# LSM303_breakout_board-v12.net
KiCad netlist of a schematic drawn in EAGLE
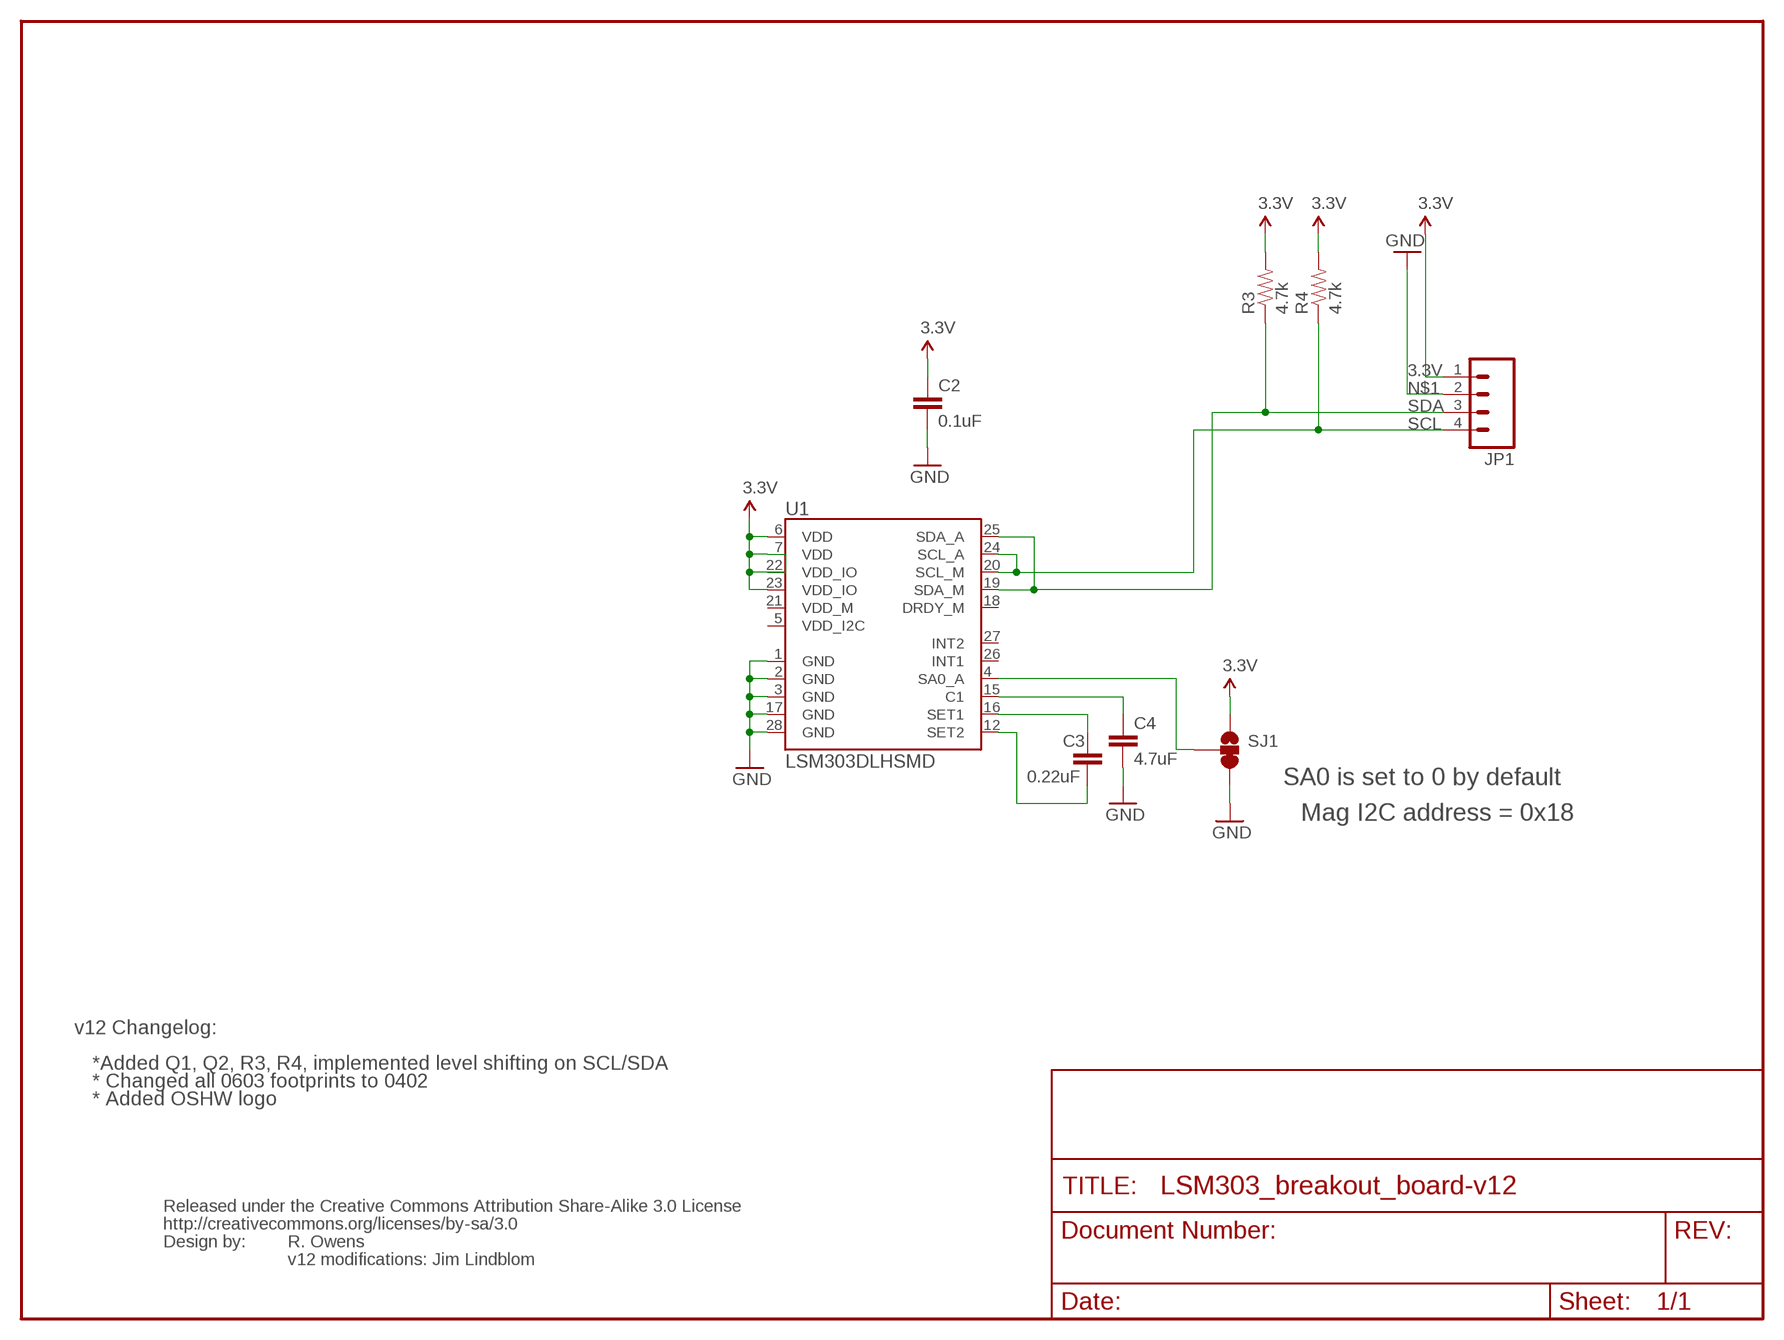
[diagram p0: schematic, sheet 1]

(export (version "E")
  (design (tool "Eeschema 10.0.6"))
  (components
    (comp (ref "C2")
      (value "0.1uF")
      (footprint "eagle-import:0603-CAP")
      (libsource (lib "eagle-import") (part "CAP0603-CAP"))
    )
    (comp (ref "C3")
      (value "0.22uF")
      (footprint "eagle-import:0603-CAP")
      (libsource (lib "eagle-import") (part "CAP0603-CAP"))
    )
    (comp (ref "C4")
      (value "4.7uF")
      (footprint "eagle-import:1206")
      (libsource (lib "eagle-import") (part "CAP1206"))
    )
    (comp (ref "JP1")
      (value "M04PTH")
      (footprint "eagle-import:1X04")
      (libsource (lib "eagle-import") (part "M04PTH"))
    )
    (comp (ref "R3")
      (value "4.7k")
      (footprint "eagle-import:0603-RES")
      (libsource (lib "eagle-import") (part "RESISTOR0603-RES"))
    )
    (comp (ref "R4")
      (value "4.7k")
      (footprint "eagle-import:0603-RES")
      (libsource (lib "eagle-import") (part "RESISTOR0603-RES"))
    )
    (comp (ref "SJ1")
      (value "SOLDERJUMPER_2WAYPASTE2&3")
      (footprint "eagle-import:SJ_3_PASTE2&3")
      (libsource (lib "eagle-import") (part "SOLDERJUMPER_2WAYPASTE2&3"))
    )
    (comp (ref "U$5")
      (value "CREATIVE_COMMONS")
      (footprint "eagle-import:CREATIVE_COMMONS")
      (libsource (lib "eagle-import") (part "CREATIVE_COMMONS"))
    )
    (comp (ref "U1")
      (value "LSM303DLHSMD")
      (footprint "eagle-import:LGA28-5X5")
      (libsource (lib "eagle-import") (part "LSM303DLHSMD"))
    )
  )
  (nets
    (net (code "1") (name "/SCL") (class "Default")
      (node (ref "JP1") (pin "4") (pinfunction "4_4") (pintype "passive"))
      (node (ref "R4") (pin "1") (pinfunction "1_1") (pintype "passive"))
      (node (ref "U1") (pin "20") (pinfunction "SCL_M_20") (pintype "bidirectional"))
      (node (ref "U1") (pin "24") (pinfunction "SCL_A_24") (pintype "bidirectional"))
    )
    (net (code "2") (name "/SDA") (class "Default")
      (node (ref "JP1") (pin "3") (pinfunction "3_3") (pintype "passive"))
      (node (ref "R3") (pin "1") (pinfunction "1_1") (pintype "passive"))
      (node (ref "U1") (pin "19") (pinfunction "SDA_M_19") (pintype "bidirectional"))
      (node (ref "U1") (pin "25") (pinfunction "SDA_A_25") (pintype "bidirectional"))
    )
    (net (code "3") (name "3.3V") (class "Default")
      (node (ref "C2") (pin "1") (pinfunction "1_1") (pintype "passive"))
      (node (ref "JP1") (pin "1") (pinfunction "1_1") (pintype "passive"))
      (node (ref "R3") (pin "2") (pinfunction "2_2") (pintype "passive"))
      (node (ref "R4") (pin "2") (pinfunction "2_2") (pintype "passive"))
      (node (ref "SJ1") (pin "1") (pinfunction "1_1") (pintype "passive"))
      (node (ref "U1") (pin "23") (pinfunction "VDD_IO_23") (pintype "bidirectional"))
      (node (ref "U1") (pin "6") (pinfunction "VDD_6") (pintype "bidirectional"))
      (node (ref "U1") (pin "7") (pinfunction "VDD_7") (pintype "bidirectional"))
    )
    (net (code "4") (name "GND") (class "Default")
      (node (ref "C2") (pin "2") (pinfunction "2_2") (pintype "passive"))
      (node (ref "C4") (pin "2") (pinfunction "2_2") (pintype "passive"))
      (node (ref "JP1") (pin "2") (pinfunction "2_2") (pintype "passive"))
      (node (ref "SJ1") (pin "3") (pinfunction "3_3") (pintype "passive"))
      (node (ref "U1") (pin "1") (pinfunction "GND_1") (pintype "bidirectional"))
      (node (ref "U1") (pin "17") (pinfunction "GND_17") (pintype "bidirectional"))
      (node (ref "U1") (pin "2") (pinfunction "GND_2") (pintype "bidirectional"))
      (node (ref "U1") (pin "28") (pinfunction "GND_28") (pintype "bidirectional"))
      (node (ref "U1") (pin "3") (pinfunction "GND_3") (pintype "bidirectional"))
    )
    (net (code "5") (name "Net-(U1-C1)") (class "Default")
      (node (ref "C4") (pin "1") (pinfunction "1_1") (pintype "passive"))
      (node (ref "U1") (pin "15") (pinfunction "C1_15") (pintype "bidirectional"))
    )
    (net (code "6") (name "Net-(U1-SA0_A)") (class "Default")
      (node (ref "SJ1") (pin "2") (pinfunction "2_2") (pintype "passive"))
      (node (ref "U1") (pin "4") (pinfunction "SA0_A_4") (pintype "bidirectional"))
    )
    (net (code "7") (name "Net-(U1-SET1)") (class "Default")
      (node (ref "C3") (pin "1") (pinfunction "1_1") (pintype "passive"))
      (node (ref "U1") (pin "16") (pinfunction "SET1_16") (pintype "bidirectional"))
    )
    (net (code "8") (name "Net-(U1-SET2)") (class "Default")
      (node (ref "C3") (pin "2") (pinfunction "2_2") (pintype "passive"))
      (node (ref "U1") (pin "12") (pinfunction "SET2_12") (pintype "bidirectional"))
    )
    (net (code "9") (name "unconnected-(U1-DRDY_M-Pad18)") (class "Default")
      (node (ref "U1") (pin "18") (pinfunction "DRDY_M_18") (pintype "bidirectional"))
    )
    (net (code "10") (name "unconnected-(U1-INT1-Pad26)") (class "Default")
      (node (ref "U1") (pin "26") (pinfunction "INT1_26") (pintype "bidirectional"))
    )
    (net (code "11") (name "unconnected-(U1-INT2-Pad27)") (class "Default")
      (node (ref "U1") (pin "27") (pinfunction "INT2_27") (pintype "bidirectional"))
    )
    (net (code "12") (name "unconnected-(U1-VDD_I2C-Pad5)") (class "Default")
      (node (ref "U1") (pin "5") (pinfunction "VDD_I2C_5") (pintype "bidirectional"))
    )
    (net (code "13") (name "unconnected-(U1-VDD_IO-Pad22)") (class "Default")
      (node (ref "U1") (pin "22") (pinfunction "VDD_IO_22") (pintype "bidirectional"))
    )
    (net (code "14") (name "unconnected-(U1-VDD_M-Pad21)") (class "Default")
      (node (ref "U1") (pin "21") (pinfunction "VDD_M_21") (pintype "bidirectional"))
    )
  )
)
